# SparkFun_XBee_Explorer_USB-C.net
KiCad netlist of a schematic drawn in EAGLE
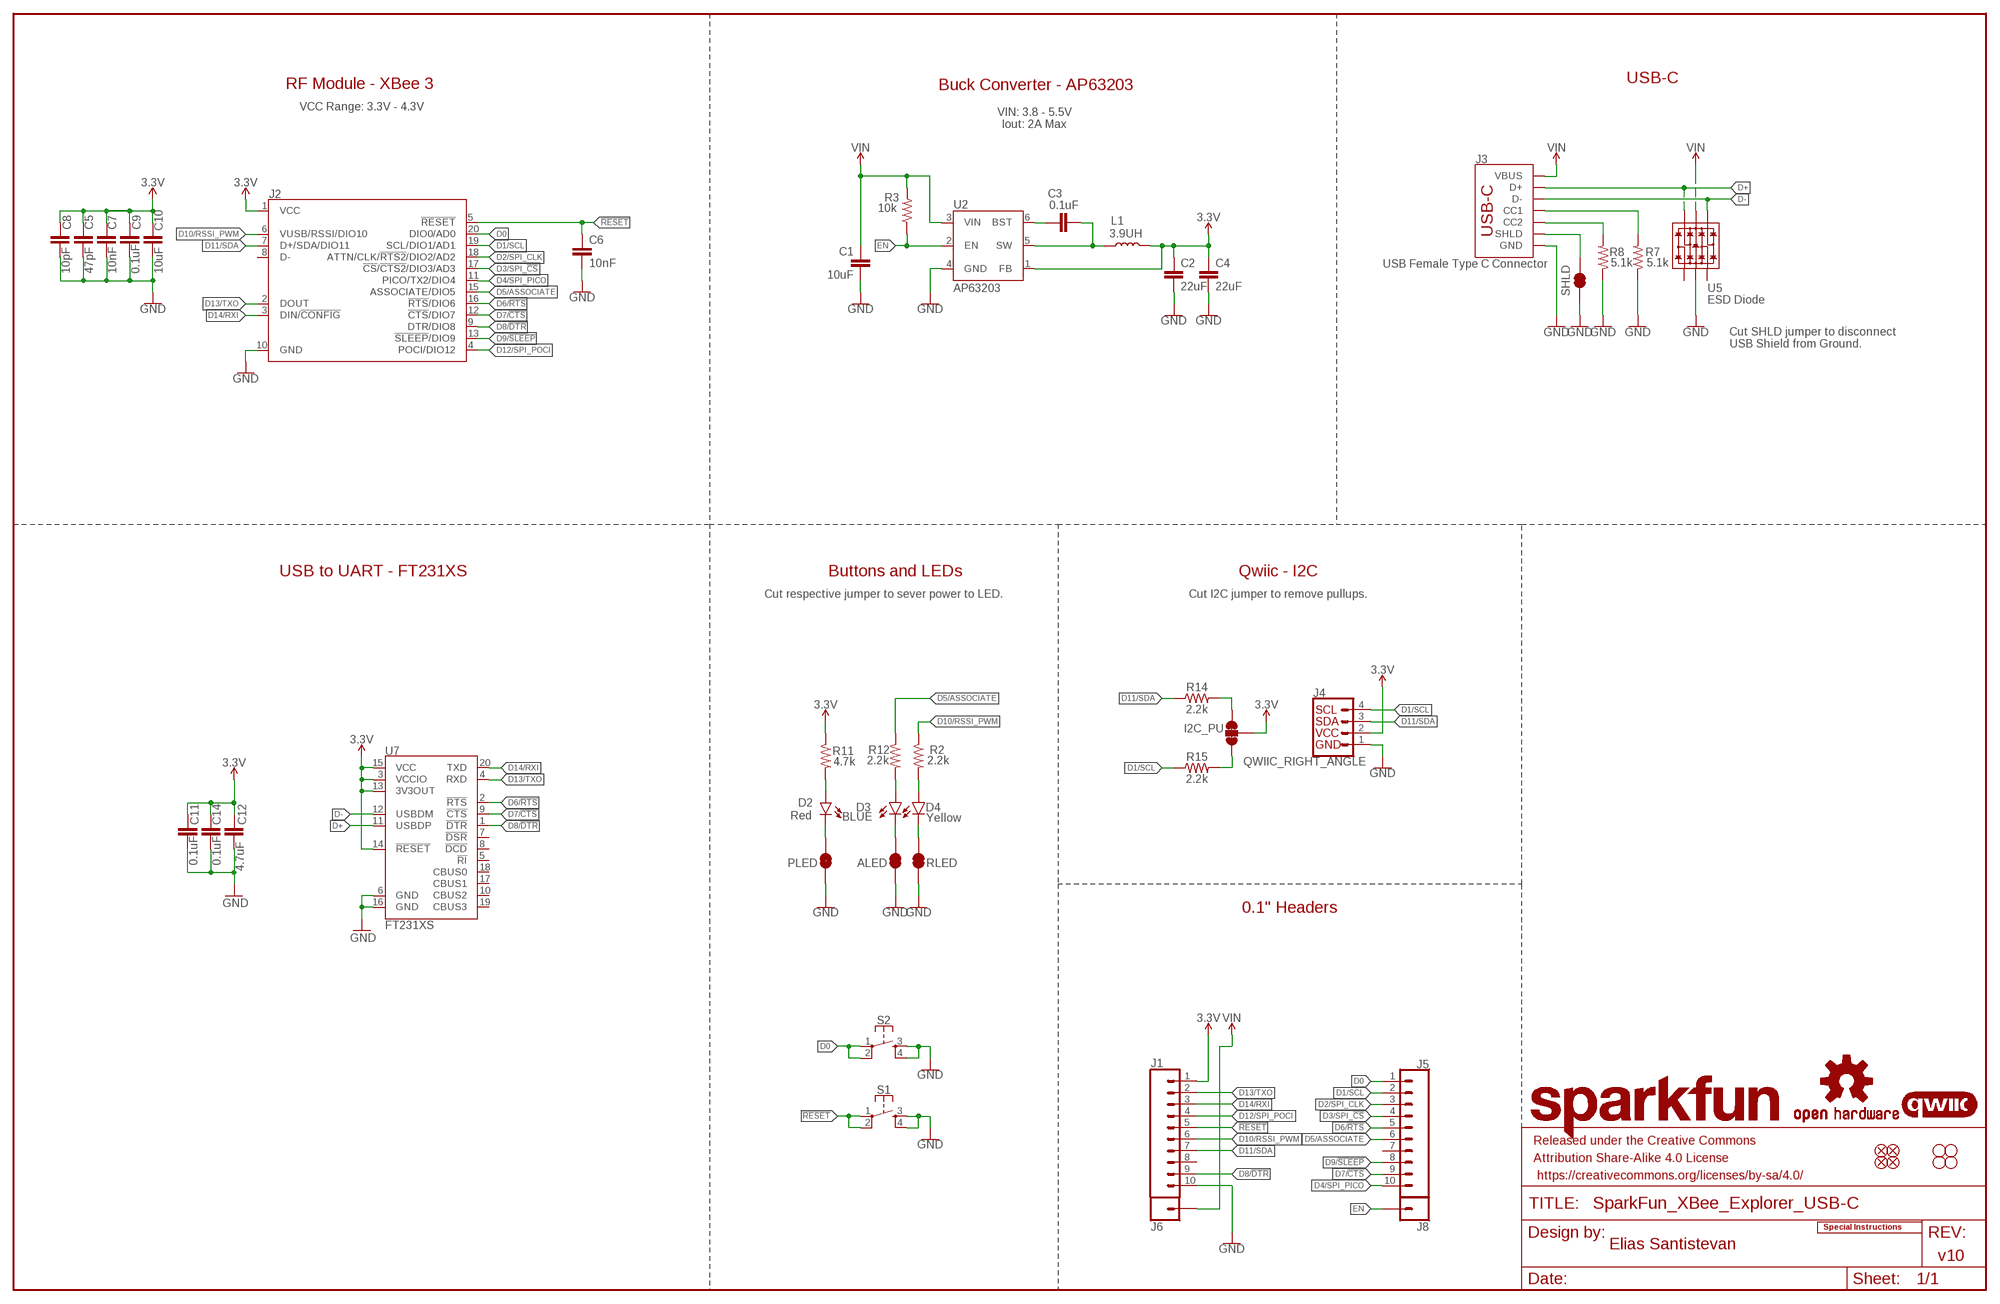
[diagram p0: schematic, sheet 1]

(export (version "E")
  (design (tool "Eeschema 10.0.6"))
  (components
    (comp (ref "ALED")
      (value "JUMPER-SMT_2_NC_TRACE_SILK")
      (footprint "eagle-import:SMT-JUMPER_2_NC_TRACE_SILK")
      (libsource (lib "eagle-import") (part "JUMPER-SMT_2_NC_TRACE_SILK"))
    )
    (comp (ref "C1")
      (value "10uF")
      (footprint "eagle-import:1210")
      (libsource (lib "eagle-import") (part "10UF-1210-50V-20%"))
    )
    (comp (ref "C2")
      (value "22uF")
      (footprint "eagle-import:0603")
      (libsource (lib "eagle-import") (part "22UF-0603-6.3V-20%"))
    )
    (comp (ref "C3")
      (value "0.1uF")
      (footprint "eagle-import:0603")
      (libsource (lib "eagle-import") (part "0.1UF-0603-25V-5%"))
    )
    (comp (ref "C4")
      (value "22uF")
      (footprint "eagle-import:0603")
      (libsource (lib "eagle-import") (part "22UF-0603-6.3V-20%"))
    )
    (comp (ref "C5")
      (value "47pF")
      (footprint "eagle-import:0603")
      (libsource (lib "eagle-import") (part "47PF-0603-50V-5%"))
    )
    (comp (ref "C6")
      (value "10nF")
      (footprint "eagle-import:0603")
      (libsource (lib "eagle-import") (part "10NF-0603-50V-10%"))
    )
    (comp (ref "C7")
      (value "10nF")
      (footprint "eagle-import:0603")
      (libsource (lib "eagle-import") (part "10NF-0603-50V-10%"))
    )
    (comp (ref "C8")
      (value "10pF")
      (footprint "eagle-import:0603")
      (libsource (lib "eagle-import") (part "10PF-0603-50V-5%"))
    )
    (comp (ref "C9")
      (value "0.1uF")
      (footprint "eagle-import:0603")
      (libsource (lib "eagle-import") (part "0.1UF-0603-25V-(+80/-20%)"))
    )
    (comp (ref "C10")
      (value "10uF")
      (footprint "eagle-import:0603")
      (libsource (lib "eagle-import") (part "10UF-0603-6.3V-20%"))
    )
    (comp (ref "C11")
      (value "0.1uF")
      (footprint "eagle-import:0603")
      (libsource (lib "eagle-import") (part "0.1UF-0603-25V-(+80/-20%)"))
    )
    (comp (ref "C12")
      (value "4.7uF")
      (footprint "eagle-import:0603")
      (libsource (lib "eagle-import") (part "4.7UF-0603-6.3V-(10%)"))
    )
    (comp (ref "C14")
      (value "0.1uF")
      (footprint "eagle-import:0603")
      (libsource (lib "eagle-import") (part "0.1UF-0603-25V-(+80/-20%)"))
    )
    (comp (ref "D2")
      (value "Red")
      (footprint "eagle-import:LED-0603")
      (libsource (lib "eagle-import") (part "LED-RED_0603-KB"))
    )
    (comp (ref "D3")
      (value "BLUE")
      (footprint "eagle-import:LED-0603")
      (libsource (lib "eagle-import") (part "LED-BLUE0603"))
    )
    (comp (ref "D4")
      (value "Yellow")
      (footprint "eagle-import:LED-0603")
      (libsource (lib "eagle-import") (part "LED-YELLOW0603"))
    )
    (comp (ref "FD1")
      (value "FIDUCIAL1X2")
      (footprint "eagle-import:FIDUCIAL-1X2")
      (libsource (lib "eagle-import") (part "FIDUCIAL1X2"))
    )
    (comp (ref "FD2")
      (value "FIDUCIAL1X2")
      (footprint "eagle-import:FIDUCIAL-1X2")
      (libsource (lib "eagle-import") (part "FIDUCIAL1X2"))
    )
    (comp (ref "FD3")
      (value "FIDUCIAL1X2")
      (footprint "eagle-import:FIDUCIAL-1X2")
      (libsource (lib "eagle-import") (part "FIDUCIAL1X2"))
    )
    (comp (ref "FD4")
      (value "FIDUCIAL1X2")
      (footprint "eagle-import:FIDUCIAL-1X2")
      (libsource (lib "eagle-import") (part "FIDUCIAL1X2"))
    )
    (comp (ref "FRAME1")
      (value "FRAME-LEDGER")
      (footprint "eagle-import:CREATIVE_COMMONS")
      (libsource (lib "eagle-import") (part "FRAME-LEDGER"))
    )
    (comp (ref "H1")
      (value "STAND-OFFTIGHT")
      (footprint "eagle-import:STAND-OFF-TIGHT")
      (libsource (lib "eagle-import") (part "STAND-OFFTIGHT"))
    )
    (comp (ref "H2")
      (value "STAND-OFFTIGHT")
      (footprint "eagle-import:STAND-OFF-TIGHT")
      (libsource (lib "eagle-import") (part "STAND-OFFTIGHT"))
    )
    (comp (ref "H3")
      (value "STAND-OFFTIGHT")
      (footprint "eagle-import:STAND-OFF-TIGHT")
      (libsource (lib "eagle-import") (part "STAND-OFFTIGHT"))
    )
    (comp (ref "H4")
      (value "STAND-OFFTIGHT")
      (footprint "eagle-import:STAND-OFF-TIGHT")
      (libsource (lib "eagle-import") (part "STAND-OFFTIGHT"))
    )
    (comp (ref "I2C_PU")
      (value "JUMPER-SMT_3_2-NC_TRACE_SILK")
      (footprint "eagle-import:SMT-JUMPER_3_2-NC_TRACE_SILK")
      (libsource (lib "eagle-import") (part "JUMPER-SMT_3_2-NC_TRACE_SILK"))
    )
    (comp (ref "J1")
      (value "CONN_01PTH_NO_SILK_STAND")
      (footprint "eagle-import:1X01_NO_SILK_STAND")
      (libsource (lib "eagle-import") (part "CONN_01PTH_NO_SILK_STAND"))
    )
    (comp (ref "J2")
      (value "XBEE_UPDATEXBEE_SMD")
      (footprint "eagle-import:XBEE3-SMD")
      (libsource (lib "eagle-import") (part "XBEE_UPDATEXBEE_SMD"))
    )
    (comp (ref "J3")
      (value "USB Female Type C Connector")
      (footprint "eagle-import:USB-C-16P-4LAYER-ISOLATED")
      (libsource (lib "eagle-import") (part "USB_C_4-LAYER-ISOLATED"))
    )
    (comp (ref "J4")
      (value "QWIIC_RIGHT_ANGLE")
      (footprint "eagle-import:JST04_1MM_RA")
      (libsource (lib "eagle-import") (part "QWIIC_CONNECTORJS-1MM"))
    )
    (comp (ref "J5")
      (value "CONN_10NO_SILK_PTH_FEMALE")
      (footprint "eagle-import:1X10_NO_SILK")
      (libsource (lib "eagle-import") (part "CONN_10NO_SILK_PTH_FEMALE"))
    )
    (comp (ref "J6")
      (value "CONN_10NO_SILK_PTH_FEMALE")
      (footprint "eagle-import:1X10_NO_SILK")
      (libsource (lib "eagle-import") (part "CONN_10NO_SILK_PTH_FEMALE"))
    )
    (comp (ref "J8")
      (value "CONN_01PTH_NO_SILK_STAND")
      (footprint "eagle-import:1X01_NO_SILK_STAND")
      (libsource (lib "eagle-import") (part "CONN_01PTH_NO_SILK_STAND"))
    )
    (comp (ref "L1")
      (value "3.9UH")
      (footprint "eagle-import:INDUCTOR_3.9UH")
      (libsource (lib "eagle-import") (part "3.9UH"))
    )
    (comp (ref "LOGO1")
      (value "SFE_LOGO_NAME.2_INCH")
      (footprint "eagle-import:SFE_LOGO_NAME_.2")
      (libsource (lib "eagle-import") (part "SFE_LOGO_NAME.2_INCH"))
    )
    (comp (ref "LOGO2")
      (value "OSHW-LOGOS")
      (footprint "eagle-import:OSHW-LOGO-S")
      (libsource (lib "eagle-import") (part "OSHW-LOGOS"))
    )
    (comp (ref "LOGO3")
      (value "QWIIC_LOGO_4MM")
      (footprint "eagle-import:QWIIC_4MM")
      (libsource (lib "eagle-import") (part "QWIIC_LOGO_4MM"))
    )
    (comp (ref "LOGO4")
      (value "SPECIAL_INSTRUCTIONS-ORDERING")
      (footprint "eagle-import:ORDERING_INSTRUCTIONS")
      (libsource (lib "eagle-import") (part "SPECIAL_INSTRUCTIONS-ORDERING"))
    )
    (comp (ref "PLED")
      (value "JUMPER-SMT_2_NC_TRACE_SILK")
      (footprint "eagle-import:SMT-JUMPER_2_NC_TRACE_SILK")
      (libsource (lib "eagle-import") (part "JUMPER-SMT_2_NC_TRACE_SILK"))
    )
    (comp (ref "R2")
      (value "2.2k")
      (footprint "eagle-import:0603")
      (libsource (lib "eagle-import") (part "2.2KOHM-0603-1/10W-1%"))
    )
    (comp (ref "R3")
      (value "10k")
      (footprint "eagle-import:0603")
      (libsource (lib "eagle-import") (part "10KOHM-0603-1/10W-1%"))
    )
    (comp (ref "R7")
      (value "5.1k")
      (footprint "eagle-import:0603")
      (libsource (lib "eagle-import") (part "5.1KOHM5.1KOHM-0603-1/10W-1%"))
    )
    (comp (ref "R8")
      (value "5.1k")
      (footprint "eagle-import:0603")
      (libsource (lib "eagle-import") (part "5.1KOHM5.1KOHM-0603-1/10W-1%"))
    )
    (comp (ref "R11")
      (value "4.7k")
      (footprint "eagle-import:0603")
      (libsource (lib "eagle-import") (part "4.7KOHM-0603-1/10W-1%"))
    )
    (comp (ref "R12")
      (value "2.2k")
      (footprint "eagle-import:0603")
      (libsource (lib "eagle-import") (part "2.2KOHM-0603-1/10W-1%"))
    )
    (comp (ref "R14")
      (value "2.2k")
      (footprint "eagle-import:0603")
      (libsource (lib "eagle-import") (part "2.2KOHM-0603-1/10W-1%"))
    )
    (comp (ref "R15")
      (value "2.2k")
      (footprint "eagle-import:0603")
      (libsource (lib "eagle-import") (part "2.2KOHM-0603-1/10W-1%"))
    )
    (comp (ref "RLED")
      (value "JUMPER-SMT_2_NC_TRACE_SILK")
      (footprint "eagle-import:SMT-JUMPER_2_NC_TRACE_SILK")
      (libsource (lib "eagle-import") (part "JUMPER-SMT_2_NC_TRACE_SILK"))
    )
    (comp (ref "S1")
      (value "MOMENTARY-SWITCH-SPST-2-SMD-5.2MM-TALL")
      (footprint "eagle-import:TACTILE_SWITCH_SMD_5.2MM")
      (libsource (lib "eagle-import") (part "MOMENTARY-SWITCH-SPST-2-SMD-5.2MM-TALL"))
    )
    (comp (ref "S2")
      (value "MOMENTARY-SWITCH-SPST-2-SMD-5.2MM-TALL")
      (footprint "eagle-import:TACTILE_SWITCH_SMD_5.2MM")
      (libsource (lib "eagle-import") (part "MOMENTARY-SWITCH-SPST-2-SMD-5.2MM-TALL"))
    )
    (comp (ref "SHLD")
      (value "JUMPER-SMT_2_NC_TRACE_SILK")
      (footprint "eagle-import:SMT-JUMPER_2_NC_TRACE_SILK")
      (libsource (lib "eagle-import") (part "JUMPER-SMT_2_NC_TRACE_SILK"))
    )
    (comp (ref "U2")
      (value "AP63203")
      (footprint "eagle-import:SOT23-6")
      (libsource (lib "eagle-import") (part "AP63203"))
    )
    (comp (ref "U5")
      (value "ESD Diode")
      (footprint "eagle-import:SOT-23-6")
      (libsource (lib "eagle-import") (part "TVS_DIODE_ARRAY_DT1042-04SO-7"))
    )
    (comp (ref "U7")
      (value "FT231XS")
      (footprint "eagle-import:SSOP20_L")
      (libsource (lib "eagle-import") (part "FT231XS"))
    )
  )
  (nets
    (net (code "1") (name "/D3{slash}SPI_~{CS}") (class "Default")
      (node (ref "J2") (pin "17") (pinfunction "~{CS}/~{CTS2}/DIO3/AD3_17") (pintype "bidirectional"))
      (node (ref "J5") (pin "4") (pinfunction "4_4") (pintype "passive"))
    )
    (net (code "2") (name "/D6{slash}~{RTS}") (class "Default")
      (node (ref "J2") (pin "16") (pinfunction "~{RTS}/DIO6_16") (pintype "input"))
      (node (ref "J5") (pin "5") (pinfunction "5_5") (pintype "passive"))
      (node (ref "U7") (pin "2") (pinfunction "~{RTS}_2") (pintype "bidirectional"))
    )
    (net (code "3") (name "/D7{slash}~{CTS}") (class "Default")
      (node (ref "J2") (pin "12") (pinfunction "~{CTS}/DIO7_12") (pintype "output"))
      (node (ref "J5") (pin "9") (pinfunction "9_9") (pintype "passive"))
      (node (ref "U7") (pin "9") (pinfunction "~{CTS}_9") (pintype "bidirectional"))
    )
    (net (code "4") (name "/D8{slash}~{DTR}") (class "Default")
      (node (ref "J2") (pin "9") (pinfunction "DTR/DIO8_9") (pintype "bidirectional"))
      (node (ref "J6") (pin "9") (pinfunction "9_9") (pintype "passive"))
      (node (ref "U7") (pin "1") (pinfunction "~{DTR}_1") (pintype "bidirectional"))
    )
    (net (code "5") (name "/D9{slash}~{SLEEP}") (class "Default")
      (node (ref "J2") (pin "13") (pinfunction "~{SLEEP}/DIO9_13") (pintype "bidirectional"))
      (node (ref "J5") (pin "8") (pinfunction "8_8") (pintype "passive"))
    )
    (net (code "6") (name "/~{RESET}") (class "Default")
      (node (ref "C6") (pin "1") (pinfunction "1_1") (pintype "passive"))
      (node (ref "J2") (pin "5") (pinfunction "~{RESET}_5") (pintype "input"))
      (node (ref "J6") (pin "5") (pinfunction "5_5") (pintype "passive"))
      (node (ref "S1") (pin "1") (pinfunction "1_1") (pintype "passive"))
      (node (ref "S1") (pin "2") (pinfunction "2_2") (pintype "passive"))
    )
    (net (code "7") (name "3.3V") (class "Default")
      (node (ref "C10") (pin "1") (pinfunction "1_1") (pintype "passive"))
      (node (ref "C11") (pin "1") (pinfunction "1_1") (pintype "passive"))
      (node (ref "C12") (pin "1") (pinfunction "1_1") (pintype "passive"))
      (node (ref "C14") (pin "1") (pinfunction "1_1") (pintype "passive"))
      (node (ref "C2") (pin "1") (pinfunction "1_1") (pintype "passive"))
      (node (ref "C4") (pin "1") (pinfunction "1_1") (pintype "passive"))
      (node (ref "C5") (pin "1") (pinfunction "1_1") (pintype "passive"))
      (node (ref "C7") (pin "1") (pinfunction "1_1") (pintype "passive"))
      (node (ref "C8") (pin "1") (pinfunction "1_1") (pintype "passive"))
      (node (ref "C9") (pin "1") (pinfunction "1_1") (pintype "passive"))
      (node (ref "I2C_PU") (pin "2") (pinfunction "2_2") (pintype "passive"))
      (node (ref "J2") (pin "1") (pinfunction "VCC_1") (pintype "power_in"))
      (node (ref "J4") (pin "2") (pinfunction "2_2") (pintype "power_in"))
      (node (ref "J6") (pin "1") (pinfunction "1_1") (pintype "passive"))
      (node (ref "L1") (pin "P$2") (pinfunction "2_P$2") (pintype "passive"))
      (node (ref "R11") (pin "1") (pinfunction "1_1") (pintype "passive"))
      (node (ref "U2") (pin "1") (pinfunction "FB_1") (pintype "bidirectional"))
      (node (ref "U7") (pin "13") (pinfunction "3V3OUT_13") (pintype "bidirectional"))
      (node (ref "U7") (pin "14") (pinfunction "~{RESET}_14") (pintype "bidirectional"))
      (node (ref "U7") (pin "15") (pinfunction "VCC_15") (pintype "bidirectional"))
      (node (ref "U7") (pin "3") (pinfunction "VCCIO_3") (pintype "bidirectional"))
    )
    (net (code "8") (name "D+") (class "Default")
      (node (ref "J3") (pin "A6") (pinfunction "D+_A6") (pintype "bidirectional"))
      (node (ref "J3") (pin "B6") (pinfunction "D+_B6") (pintype "bidirectional"))
      (node (ref "U5") (pin "6") (pinfunction "IO4_6") (pintype "bidirectional"))
      (node (ref "U7") (pin "11") (pinfunction "USBDP_11") (pintype "bidirectional"))
    )
    (net (code "9") (name "D-") (class "Default")
      (node (ref "J3") (pin "A7") (pinfunction "D-_A7") (pintype "bidirectional"))
      (node (ref "J3") (pin "B7") (pinfunction "D-_B7") (pintype "bidirectional"))
      (node (ref "U5") (pin "4") (pinfunction "IO3_4") (pintype "bidirectional"))
      (node (ref "U7") (pin "12") (pinfunction "USBDM_12") (pintype "bidirectional"))
    )
    (net (code "10") (name "D0") (class "Default")
      (node (ref "J2") (pin "20") (pinfunction "DIO0/AD0_20") (pintype "bidirectional"))
      (node (ref "J5") (pin "1") (pinfunction "1_1") (pintype "passive"))
      (node (ref "S2") (pin "1") (pinfunction "1_1") (pintype "passive"))
      (node (ref "S2") (pin "2") (pinfunction "2_2") (pintype "passive"))
    )
    (net (code "11") (name "D1{slash}SCL") (class "Default")
      (node (ref "J2") (pin "19") (pinfunction "SCL/DIO1/AD1_19") (pintype "bidirectional"))
      (node (ref "J4") (pin "4") (pinfunction "4_4") (pintype "passive"))
      (node (ref "J5") (pin "2") (pinfunction "2_2") (pintype "passive"))
      (node (ref "R15") (pin "1") (pinfunction "1_1") (pintype "passive"))
    )
    (net (code "12") (name "D2{slash}SPI_CLK") (class "Default")
      (node (ref "J2") (pin "18") (pinfunction "ATTN/CLK/~{RTS2}/DIO2/AD2_18") (pintype "bidirectional"))
      (node (ref "J5") (pin "3") (pinfunction "3_3") (pintype "passive"))
    )
    (net (code "13") (name "D4{slash}SPI_PICO") (class "Default")
      (node (ref "J2") (pin "11") (pinfunction "PICO/TX2/DIO4_11") (pintype "bidirectional"))
      (node (ref "J5") (pin "10") (pinfunction "10_10") (pintype "passive"))
    )
    (net (code "14") (name "D5{slash}ASSOCIATE") (class "Default")
      (node (ref "J2") (pin "15") (pinfunction "ASSOCIATE/DIO5_15") (pintype "bidirectional"))
      (node (ref "J5") (pin "6") (pinfunction "6_6") (pintype "passive"))
      (node (ref "R12") (pin "1") (pinfunction "1_1") (pintype "passive"))
    )
    (net (code "15") (name "D10{slash}RSSI_PWM") (class "Default")
      (node (ref "J2") (pin "6") (pinfunction "VUSB/RSSI/DIO10_6") (pintype "bidirectional"))
      (node (ref "J6") (pin "6") (pinfunction "6_6") (pintype "passive"))
      (node (ref "R2") (pin "1") (pinfunction "1_1") (pintype "passive"))
    )
    (net (code "16") (name "D11{slash}SDA") (class "Default")
      (node (ref "J2") (pin "7") (pinfunction "D+/SDA/DIO11_7") (pintype "bidirectional"))
      (node (ref "J4") (pin "3") (pinfunction "3_3") (pintype "passive"))
      (node (ref "J6") (pin "7") (pinfunction "7_7") (pintype "passive"))
      (node (ref "R14") (pin "1") (pinfunction "1_1") (pintype "passive"))
    )
    (net (code "17") (name "D12{slash}SPI_POCI") (class "Default")
      (node (ref "J2") (pin "4") (pinfunction "POCI/DIO12_4") (pintype "bidirectional"))
      (node (ref "J6") (pin "4") (pinfunction "4_4") (pintype "passive"))
    )
    (net (code "18") (name "D13{slash}TXO") (class "Default")
      (node (ref "J2") (pin "2") (pinfunction "DOUT_2") (pintype "output"))
      (node (ref "J6") (pin "2") (pinfunction "2_2") (pintype "passive"))
      (node (ref "U7") (pin "4") (pinfunction "RXD_4") (pintype "bidirectional"))
    )
    (net (code "19") (name "D14{slash}RXI") (class "Default")
      (node (ref "J2") (pin "3") (pinfunction "DIN/~{CONFIG}_3") (pintype "input"))
      (node (ref "J6") (pin "3") (pinfunction "3_3") (pintype "passive"))
      (node (ref "U7") (pin "20") (pinfunction "TXD_20") (pintype "bidirectional"))
    )
    (net (code "20") (name "EN") (class "Default")
      (node (ref "J8") (pin "1") (pinfunction "1_1") (pintype "passive"))
      (node (ref "R3") (pin "1") (pinfunction "1_1") (pintype "passive"))
      (node (ref "U2") (pin "2") (pinfunction "EN_2") (pintype "bidirectional"))
    )
    (net (code "21") (name "GND") (class "Default")
      (node (ref "ALED") (pin "1") (pinfunction "1_1") (pintype "passive"))
      (node (ref "C1") (pin "2") (pinfunction "2_2") (pintype "passive"))
      (node (ref "C10") (pin "2") (pinfunction "2_2") (pintype "passive"))
      (node (ref "C11") (pin "2") (pinfunction "2_2") (pintype "passive"))
      (node (ref "C12") (pin "2") (pinfunction "2_2") (pintype "passive"))
      (node (ref "C14") (pin "2") (pinfunction "2_2") (pintype "passive"))
      (node (ref "C2") (pin "2") (pinfunction "2_2") (pintype "passive"))
      (node (ref "C4") (pin "2") (pinfunction "2_2") (pintype "passive"))
      (node (ref "C5") (pin "2") (pinfunction "2_2") (pintype "passive"))
      (node (ref "C6") (pin "2") (pinfunction "2_2") (pintype "passive"))
      (node (ref "C7") (pin "2") (pinfunction "2_2") (pintype "passive"))
      (node (ref "C8") (pin "2") (pinfunction "2_2") (pintype "passive"))
      (node (ref "C9") (pin "2") (pinfunction "2_2") (pintype "passive"))
      (node (ref "J2") (pin "10") (pinfunction "GND_10") (pintype "power_in"))
      (node (ref "J3") (pin "GND") (pinfunction "GND_GND") (pintype "bidirectional"))
      (node (ref "J3") (pin "GND2") (pinfunction "GND_GND2") (pintype "bidirectional"))
      (node (ref "J4") (pin "1") (pinfunction "1_1") (pintype "power_in"))
      (node (ref "J6") (pin "10") (pinfunction "10_10") (pintype "passive"))
      (node (ref "PLED") (pin "1") (pinfunction "1_1") (pintype "passive"))
      (node (ref "R7") (pin "1") (pinfunction "1_1") (pintype "passive"))
      (node (ref "R8") (pin "1") (pinfunction "1_1") (pintype "passive"))
      (node (ref "RLED") (pin "1") (pinfunction "1_1") (pintype "passive"))
      (node (ref "S1") (pin "3") (pinfunction "3_3") (pintype "passive"))
      (node (ref "S1") (pin "4") (pinfunction "4_4") (pintype "passive"))
      (node (ref "S2") (pin "3") (pinfunction "3_3") (pintype "passive"))
      (node (ref "S2") (pin "4") (pinfunction "4_4") (pintype "passive"))
      (node (ref "SHLD") (pin "1") (pinfunction "1_1") (pintype "passive"))
      (node (ref "U2") (pin "4") (pinfunction "GND_4") (pintype "bidirectional"))
      (node (ref "U5") (pin "2") (pinfunction "VSS_2") (pintype "bidirectional"))
      (node (ref "U7") (pin "16") (pinfunction "GND_16") (pintype "bidirectional"))
      (node (ref "U7") (pin "6") (pinfunction "GND_6") (pintype "bidirectional"))
    )
    (net (code "22") (name "Net-(ALED-Pad2)") (class "Default")
      (node (ref "ALED") (pin "2") (pinfunction "2_2") (pintype "passive"))
      (node (ref "D3") (pin "C") (pinfunction "C_C") (pintype "passive"))
    )
    (net (code "23") (name "Net-(D2-PadA)") (class "Default")
      (node (ref "D2") (pin "A") (pinfunction "A_A") (pintype "passive"))
      (node (ref "R11") (pin "2") (pinfunction "2_2") (pintype "passive"))
    )
    (net (code "24") (name "Net-(D2-PadC)") (class "Default")
      (node (ref "D2") (pin "C") (pinfunction "C_C") (pintype "passive"))
      (node (ref "PLED") (pin "2") (pinfunction "2_2") (pintype "passive"))
    )
    (net (code "25") (name "Net-(D3-PadA)") (class "Default")
      (node (ref "D3") (pin "A") (pinfunction "A_A") (pintype "passive"))
      (node (ref "R12") (pin "2") (pinfunction "2_2") (pintype "passive"))
    )
    (net (code "26") (name "Net-(D4-PadA)") (class "Default")
      (node (ref "D4") (pin "A") (pinfunction "A_A") (pintype "passive"))
      (node (ref "R2") (pin "2") (pinfunction "2_2") (pintype "passive"))
    )
    (net (code "27") (name "Net-(D4-PadC)") (class "Default")
      (node (ref "D4") (pin "C") (pinfunction "C_C") (pintype "passive"))
      (node (ref "RLED") (pin "2") (pinfunction "2_2") (pintype "passive"))
    )
    (net (code "28") (name "Net-(I2C_PU-Pad1)") (class "Default")
      (node (ref "I2C_PU") (pin "1") (pinfunction "1_1") (pintype "passive"))
      (node (ref "R15") (pin "2") (pinfunction "2_2") (pintype "passive"))
    )
    (net (code "29") (name "Net-(I2C_PU-Pad3)") (class "Default")
      (node (ref "I2C_PU") (pin "3") (pinfunction "3_3") (pintype "passive"))
      (node (ref "R14") (pin "2") (pinfunction "2_2") (pintype "passive"))
    )
    (net (code "30") (name "Net-(J3-CC1)") (class "Default")
      (node (ref "J3") (pin "A5") (pinfunction "CC1_A5") (pintype "bidirectional"))
      (node (ref "R7") (pin "2") (pinfunction "2_2") (pintype "passive"))
    )
    (net (code "31") (name "Net-(J3-CC2)") (class "Default")
      (node (ref "J3") (pin "B5") (pinfunction "CC2_B5") (pintype "bidirectional"))
      (node (ref "R8") (pin "2") (pinfunction "2_2") (pintype "passive"))
    )
    (net (code "32") (name "Net-(J3-SHLD-PadSHLD1)") (class "Default")
      (node (ref "J3") (pin "SHLD1") (pinfunction "SHLD_SHLD1") (pintype "bidirectional"))
      (node (ref "J3") (pin "SHLD2") (pinfunction "SHLD_SHLD2") (pintype "bidirectional"))
      (node (ref "J3") (pin "SHLD3") (pinfunction "SHLD_SHLD3") (pintype "bidirectional"))
      (node (ref "J3") (pin "SHLD4") (pinfunction "SHLD_SHLD4") (pintype "bidirectional"))
      (node (ref "J3") (pin "SHLD5") (pinfunction "SHLD_SHLD5") (pintype "bidirectional"))
      (node (ref "J3") (pin "SHLD6") (pinfunction "SHLD_SHLD6") (pintype "bidirectional"))
      (node (ref "J3") (pin "SHLD7") (pinfunction "SHLD_SHLD7") (pintype "bidirectional"))
      (node (ref "J3") (pin "SHLD8") (pinfunction "SHLD_SHLD8") (pintype "bidirectional"))
      (node (ref "SHLD") (pin "2") (pinfunction "2_2") (pintype "passive"))
    )
    (net (code "33") (name "Net-(L1-1)") (class "Default")
      (node (ref "C3") (pin "2") (pinfunction "2_2") (pintype "passive"))
      (node (ref "L1") (pin "P$1") (pinfunction "1_P$1") (pintype "passive"))
      (node (ref "U2") (pin "5") (pinfunction "SW_5") (pintype "bidirectional"))
    )
    (net (code "34") (name "Net-(U2-BST)") (class "Default")
      (node (ref "C3") (pin "1") (pinfunction "1_1") (pintype "passive"))
      (node (ref "U2") (pin "6") (pinfunction "BST_6") (pintype "bidirectional"))
    )
    (net (code "35") (name "VIN") (class "Default")
      (node (ref "C1") (pin "1") (pinfunction "1_1") (pintype "passive"))
      (node (ref "J1") (pin "1") (pinfunction "1_1") (pintype "passive"))
      (node (ref "J3") (pin "VBUS1") (pinfunction "VBUS_VBUS1") (pintype "bidirectional"))
      (node (ref "J3") (pin "VBUS2") (pinfunction "VBUS_VBUS2") (pintype "bidirectional"))
      (node (ref "R3") (pin "2") (pinfunction "2_2") (pintype "passive"))
      (node (ref "U2") (pin "3") (pinfunction "VIN_3") (pintype "bidirectional"))
      (node (ref "U5") (pin "5") (pinfunction "VCC_5") (pintype "bidirectional"))
    )
    (net (code "36") (name "unconnected-(J2-D--Pad8)") (class "Default")
      (node (ref "J2") (pin "8") (pinfunction "D-_8") (pintype "bidirectional"))
    )
    (net (code "37") (name "unconnected-(J5-Pad7)") (class "Default")
      (node (ref "J5") (pin "7") (pinfunction "7_7") (pintype "passive"))
    )
    (net (code "38") (name "unconnected-(J6-Pad8)") (class "Default")
      (node (ref "J6") (pin "8") (pinfunction "8_8") (pintype "passive"))
    )
    (net (code "39") (name "unconnected-(U5-IO1-Pad1)") (class "Default")
      (node (ref "U5") (pin "1") (pinfunction "IO1_1") (pintype "bidirectional"))
    )
    (net (code "40") (name "unconnected-(U5-IO2-Pad3)") (class "Default")
      (node (ref "U5") (pin "3") (pinfunction "IO2_3") (pintype "bidirectional"))
    )
    (net (code "41") (name "unconnected-(U7-CBUS0-Pad18)") (class "Default")
      (node (ref "U7") (pin "18") (pinfunction "CBUS0_18") (pintype "bidirectional"))
    )
    (net (code "42") (name "unconnected-(U7-CBUS1-Pad17)") (class "Default")
      (node (ref "U7") (pin "17") (pinfunction "CBUS1_17") (pintype "bidirectional"))
    )
    (net (code "43") (name "unconnected-(U7-CBUS2-Pad10)") (class "Default")
      (node (ref "U7") (pin "10") (pinfunction "CBUS2_10") (pintype "bidirectional"))
    )
    (net (code "44") (name "unconnected-(U7-CBUS3-Pad19)") (class "Default")
      (node (ref "U7") (pin "19") (pinfunction "CBUS3_19") (pintype "bidirectional"))
    )
    (net (code "45") (name "unconnected-(U7-~{DCD}-Pad8)") (class "Default")
      (node (ref "U7") (pin "8") (pinfunction "~{DCD}_8") (pintype "bidirectional"))
    )
    (net (code "46") (name "unconnected-(U7-~{DSR}-Pad7)") (class "Default")
      (node (ref "U7") (pin "7") (pinfunction "~{DSR}_7") (pintype "bidirectional"))
    )
    (net (code "47") (name "unconnected-(U7-~{RI}-Pad5)") (class "Default")
      (node (ref "U7") (pin "5") (pinfunction "~{RI}_5") (pintype "bidirectional"))
    )
  )
)
